# P5a_Filter1A.net
KiCad netlist of a schematic drawn in Altium Designer
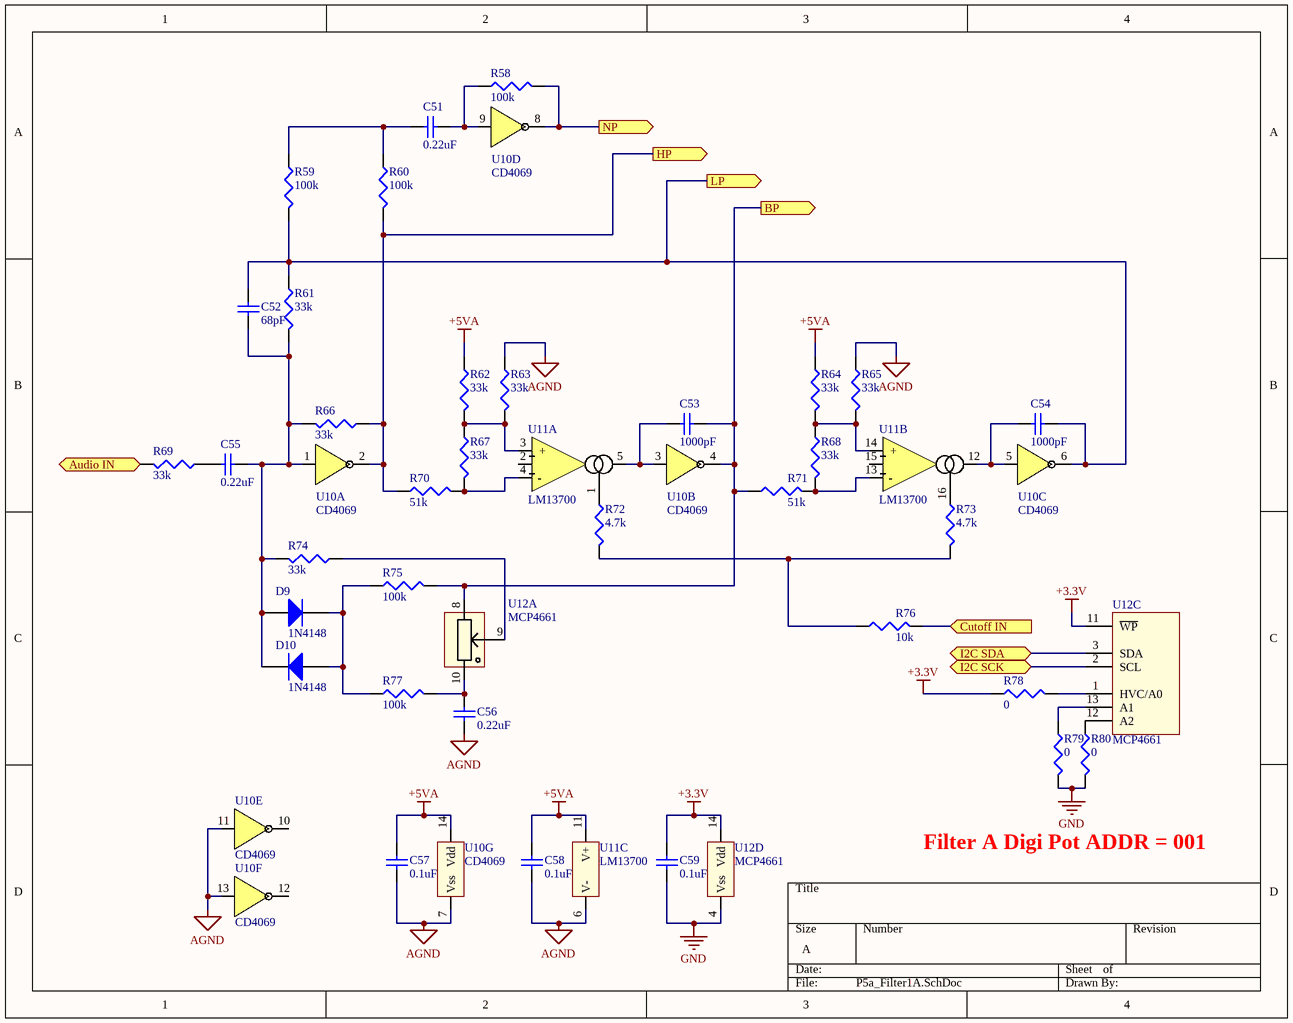
[diagram p0: P5a_Filter1A.SchDoc]

(export (version "E")
  (design (tool "Eeschema 10.0.6"))
  (components
    (comp (ref "C51")
      (value "0.22uF")
      (footprint "CAP 0603 (1608 metric)")
      (description "Capacitor (Semiconductor SIM Model)")
      (libsource (lib "Miscellaneous Devices") (part "Cap Semi"))
    )
    (comp (ref "C52")
      (value "68pF")
      (footprint "CAP 0603 (1608 metric)")
      (description "Capacitor (Semiconductor SIM Model)")
      (libsource (lib "Miscellaneous Devices") (part "Cap Semi"))
    )
    (comp (ref "C53")
      (value "1000pF")
      (footprint "CAP 0603 (1608 metric)")
      (description "Capacitor (Semiconductor SIM Model)")
      (libsource (lib "Miscellaneous Devices") (part "Cap Semi"))
    )
    (comp (ref "C54")
      (value "1000pF")
      (footprint "CAP 0603 (1608 metric)")
      (description "Capacitor (Semiconductor SIM Model)")
      (libsource (lib "Miscellaneous Devices") (part "Cap Semi"))
    )
    (comp (ref "C55")
      (value "0.22uF")
      (footprint "CAP 0603 (1608 metric)")
      (description "Capacitor (Semiconductor SIM Model)")
      (libsource (lib "Miscellaneous Devices") (part "Cap Semi"))
    )
    (comp (ref "C56")
      (value "0.22uF")
      (footprint "CAP 0603 (1608 metric)")
      (description "Capacitor (Semiconductor SIM Model)")
      (libsource (lib "Miscellaneous Devices") (part "Cap Semi"))
    )
    (comp (ref "C57")
      (value "0.1uF")
      (footprint "CAP 0603 (1608 metric)")
      (description "Capacitor (Semiconductor SIM Model)")
      (libsource (lib "Miscellaneous Devices") (part "Cap Semi"))
    )
    (comp (ref "C58")
      (value "0.1uF")
      (footprint "CAP 0603 (1608 metric)")
      (description "Capacitor (Semiconductor SIM Model)")
      (libsource (lib "Miscellaneous Devices") (part "Cap Semi"))
    )
    (comp (ref "C59")
      (value "0.1uF")
      (footprint "CAP 0603 (1608 metric)")
      (description "Capacitor (Semiconductor SIM Model)")
      (libsource (lib "Miscellaneous Devices") (part "Cap Semi"))
    )
    (comp (ref "D9")
      (value "1N4148")
      (description "High Conductance Fast Diode")
      (libsource (lib "Miscellaneous Devices") (part "Diode 1N4148"))
    )
    (comp (ref "D10")
      (value "1N4148")
      (description "High Conductance Fast Diode")
      (libsource (lib "Miscellaneous Devices") (part "Diode 1N4148"))
    )
    (comp (ref "R58")
      (value "100k")
      (footprint "RES 0603 (1608 metric)")
      (description "Resistor")
      (libsource (lib "Miscellaneous Devices") (part "Res3"))
    )
    (comp (ref "R59")
      (value "100k")
      (footprint "RES 0603 (1608 metric)")
      (description "Resistor")
      (libsource (lib "Miscellaneous Devices") (part "Res3"))
    )
    (comp (ref "R60")
      (value "100k")
      (footprint "RES 0603 (1608 metric)")
      (description "Resistor")
      (libsource (lib "Miscellaneous Devices") (part "Res3"))
    )
    (comp (ref "R61")
      (value "33k")
      (footprint "RES 0603 (1608 metric)")
      (description "Resistor")
      (libsource (lib "Miscellaneous Devices") (part "Res3"))
    )
    (comp (ref "R62")
      (value "33k")
      (footprint "RES 0603 (1608 metric)")
      (description "Resistor")
      (libsource (lib "Miscellaneous Devices") (part "Res3"))
    )
    (comp (ref "R63")
      (value "33k")
      (footprint "RES 0603 (1608 metric)")
      (description "Resistor")
      (libsource (lib "Miscellaneous Devices") (part "Res3"))
    )
    (comp (ref "R64")
      (value "33k")
      (footprint "RES 0603 (1608 metric)")
      (description "Resistor")
      (libsource (lib "Miscellaneous Devices") (part "Res3"))
    )
    (comp (ref "R65")
      (value "33k")
      (footprint "RES 0603 (1608 metric)")
      (description "Resistor")
      (libsource (lib "Miscellaneous Devices") (part "Res3"))
    )
    (comp (ref "R66")
      (value "33k")
      (footprint "RES 0603 (1608 metric)")
      (description "Resistor")
      (libsource (lib "Miscellaneous Devices") (part "Res3"))
    )
    (comp (ref "R67")
      (value "33k")
      (footprint "RES 0603 (1608 metric)")
      (description "Resistor")
      (libsource (lib "Miscellaneous Devices") (part "Res3"))
    )
    (comp (ref "R68")
      (value "33k")
      (footprint "RES 0603 (1608 metric)")
      (description "Resistor")
      (libsource (lib "Miscellaneous Devices") (part "Res3"))
    )
    (comp (ref "R69")
      (value "33k")
      (footprint "RES 0603 (1608 metric)")
      (description "Resistor")
      (libsource (lib "Miscellaneous Devices") (part "Res3"))
    )
    (comp (ref "R70")
      (value "51k")
      (footprint "RES 0603 (1608 metric)")
      (description "Resistor")
      (libsource (lib "Miscellaneous Devices") (part "Res3"))
    )
    (comp (ref "R71")
      (value "51k")
      (footprint "RES 0603 (1608 metric)")
      (description "Resistor")
      (libsource (lib "Miscellaneous Devices") (part "Res3"))
    )
    (comp (ref "R72")
      (value "4.7k")
      (footprint "RES 0603 (1608 metric)")
      (description "Resistor")
      (libsource (lib "Miscellaneous Devices") (part "Res3"))
    )
    (comp (ref "R73")
      (value "4.7k")
      (footprint "RES 0603 (1608 metric)")
      (description "Resistor")
      (libsource (lib "Miscellaneous Devices") (part "Res3"))
    )
    (comp (ref "R74")
      (value "33k")
      (footprint "RES 0603 (1608 metric)")
      (description "Resistor")
      (libsource (lib "Miscellaneous Devices") (part "Res3"))
    )
    (comp (ref "R75")
      (value "100k")
      (footprint "RES 0603 (1608 metric)")
      (description "Resistor")
      (libsource (lib "Miscellaneous Devices") (part "Res3"))
    )
    (comp (ref "R76")
      (value "10k")
      (footprint "RES 0603 (1608 metric)")
      (description "Resistor")
      (libsource (lib "Miscellaneous Devices") (part "Res3"))
    )
    (comp (ref "R77")
      (value "100k")
      (footprint "RES 0603 (1608 metric)")
      (description "Resistor")
      (libsource (lib "Miscellaneous Devices") (part "Res3"))
    )
    (comp (ref "R78")
      (value "0")
      (footprint "RES 0603 (1608 metric)")
      (description "Resistor")
      (libsource (lib "Miscellaneous Devices") (part "Res3"))
    )
    (comp (ref "R79")
      (value "0")
      (footprint "RES 0603 (1608 metric)")
      (description "Resistor")
      (libsource (lib "Miscellaneous Devices") (part "Res3"))
    )
    (comp (ref "R80")
      (value "0")
      (footprint "RES 0603 (1608 metric)")
      (description "Resistor")
      (libsource (lib "Miscellaneous Devices") (part "Res3"))
    )
    (comp (ref "U10")
      (value "CD4069")
      (description "Hex Inverter")
      (libsource (lib "FilterPoC") (part "CD4069"))
    )
    (comp (ref "U11")
      (value "LM13700")
      (description "Dual Transconductance OpAmp")
      (libsource (lib "FilterPoC") (part "LM13700M"))
    )
    (comp (ref "U12")
      (value "MCP4661")
      (description "Dual DigiPot non volatile I2C")
      (libsource (lib "FilterPoC") (part "MCP4661"))
    )
  )
  (nets
    (net (code "1") (name "+3.3V") (class "Default")
      (node (ref "C59") (pin "1") (pinfunction "1_1") (pintype "passive"))
      (node (ref "R78") (pin "1") (pinfunction "1_1") (pintype "passive"))
      (node (ref "U12") (pin "11") (pinfunction "~{WP}_11") (pintype "passive"))
      (node (ref "U12") (pin "14") (pinfunction "Vdd_14") (pintype "power_in"))
    )
    (net (code "2") (name "+5VA") (class "Default")
      (node (ref "C57") (pin "1") (pinfunction "1_1") (pintype "passive"))
      (node (ref "C58") (pin "1") (pinfunction "1_1") (pintype "passive"))
      (node (ref "R62") (pin "1") (pinfunction "1_1") (pintype "passive"))
      (node (ref "R64") (pin "1") (pinfunction "1_1") (pintype "passive"))
      (node (ref "U10") (pin "14") (pinfunction "Vdd_14") (pintype "power_in"))
      (node (ref "U11") (pin "11") (pinfunction "V+_11") (pintype "power_in"))
    )
    (net (code "3") (name "/Audio IN") (class "Default")
      (node (ref "R69") (pin "2") (pinfunction "2_2") (pintype "passive"))
    )
    (net (code "4") (name "/BP") (class "Default")
      (node (ref "C53") (pin "2") (pinfunction "2_2") (pintype "passive"))
      (node (ref "R71") (pin "1") (pinfunction "1_1") (pintype "passive"))
      (node (ref "R75") (pin "2") (pinfunction "2_2") (pintype "passive"))
      (node (ref "U10") (pin "4") (pinfunction "~{B}_4") (pintype "passive"))
      (node (ref "U12") (pin "8") (pinfunction "P0A_8") (pintype "passive"))
    )
    (net (code "5") (name "/Cutoff IN") (class "Default")
      (node (ref "R76") (pin "2") (pinfunction "2_2") (pintype "passive"))
    )
    (net (code "6") (name "/HP") (class "Default")
      (node (ref "R60") (pin "2") (pinfunction "2_2") (pintype "passive"))
      (node (ref "R66") (pin "1") (pinfunction "1_1") (pintype "passive"))
      (node (ref "R70") (pin "1") (pinfunction "1_1") (pintype "passive"))
      (node (ref "U10") (pin "2") (pinfunction "~{A}_2") (pintype "passive"))
    )
    (net (code "7") (name "/I2C SCK") (class "Default")
      (node (ref "U12") (pin "2") (pinfunction "SCL_2") (pintype "passive"))
    )
    (net (code "8") (name "/I2C SDA") (class "Default")
      (node (ref "U12") (pin "3") (pinfunction "SDA_3") (pintype "passive"))
    )
    (net (code "9") (name "/LP") (class "Default")
      (node (ref "C52") (pin "2") (pinfunction "2_2") (pintype "passive"))
      (node (ref "C54") (pin "2") (pinfunction "2_2") (pintype "passive"))
      (node (ref "R59") (pin "2") (pinfunction "2_2") (pintype "passive"))
      (node (ref "R61") (pin "1") (pinfunction "1_1") (pintype "passive"))
      (node (ref "U10") (pin "6") (pinfunction "~{C}_6") (pintype "passive"))
    )
    (net (code "10") (name "/NP") (class "Default")
      (node (ref "R58") (pin "2") (pinfunction "2_2") (pintype "passive"))
      (node (ref "U10") (pin "8") (pinfunction "~{D}_8") (pintype "passive"))
    )
    (net (code "11") (name "AGND") (class "Default")
      (node (ref "C56") (pin "2") (pinfunction "2_2") (pintype "passive"))
      (node (ref "C57") (pin "2") (pinfunction "2_2") (pintype "passive"))
      (node (ref "C58") (pin "2") (pinfunction "2_2") (pintype "passive"))
      (node (ref "R63") (pin "1") (pinfunction "1_1") (pintype "passive"))
      (node (ref "R65") (pin "1") (pinfunction "1_1") (pintype "passive"))
      (node (ref "U10") (pin "11") (pinfunction "E_11") (pintype "passive"))
      (node (ref "U10") (pin "13") (pinfunction "F_13") (pintype "passive"))
      (node (ref "U10") (pin "7") (pinfunction "Vss_7") (pintype "power_in"))
      (node (ref "U11") (pin "6") (pinfunction "V-_6") (pintype "power_in"))
    )
    (net (code "12") (name "GND") (class "Default")
      (node (ref "C59") (pin "2") (pinfunction "2_2") (pintype "passive"))
      (node (ref "R79") (pin "2") (pinfunction "2_2") (pintype "passive"))
      (node (ref "R80") (pin "2") (pinfunction "2_2") (pintype "passive"))
      (node (ref "U12") (pin "4") (pinfunction "Vss_4") (pintype "power_in"))
    )
    (net (code "13") (name "Net-(C51-Pad1)") (class "Default")
      (node (ref "C51") (pin "1") (pinfunction "1_1") (pintype "passive"))
      (node (ref "R59") (pin "1") (pinfunction "1_1") (pintype "passive"))
      (node (ref "R60") (pin "1") (pinfunction "1_1") (pintype "passive"))
    )
    (net (code "14") (name "Net-(C55-Pad1)") (class "Default")
      (node (ref "C55") (pin "1") (pinfunction "1_1") (pintype "passive"))
      (node (ref "R69") (pin "1") (pinfunction "1_1") (pintype "passive"))
    )
    (net (code "15") (name "Net-(D10-A)") (class "Default")
      (node (ref "D10") (pin "1") (pinfunction "A_1") (pintype "passive"))
      (node (ref "D9") (pin "2") (pinfunction "K_2") (pintype "passive"))
      (node (ref "R75") (pin "1") (pinfunction "1_1") (pintype "passive"))
      (node (ref "R77") (pin "1") (pinfunction "1_1") (pintype "passive"))
    )
    (net (code "16") (name "Net-(D10-K)") (class "Default")
      (node (ref "C52") (pin "1") (pinfunction "1_1") (pintype "passive"))
      (node (ref "C55") (pin "2") (pinfunction "2_2") (pintype "passive"))
      (node (ref "D10") (pin "2") (pinfunction "K_2") (pintype "passive"))
      (node (ref "D9") (pin "1") (pinfunction "A_1") (pintype "passive"))
      (node (ref "R61") (pin "2") (pinfunction "2_2") (pintype "passive"))
      (node (ref "R66") (pin "2") (pinfunction "2_2") (pintype "passive"))
      (node (ref "R74") (pin "2") (pinfunction "2_2") (pintype "passive"))
      (node (ref "U10") (pin "1") (pinfunction "A_1") (pintype "passive"))
    )
    (net (code "17") (name "Net-(R72-Pad2)") (class "Default")
      (node (ref "R72") (pin "2") (pinfunction "2_2") (pintype "passive"))
      (node (ref "R73") (pin "2") (pinfunction "2_2") (pintype "passive"))
      (node (ref "R76") (pin "1") (pinfunction "1_1") (pintype "passive"))
    )
    (net (code "18") (name "Net-(U10B-B)") (class "Default")
      (node (ref "C53") (pin "1") (pinfunction "1_1") (pintype "passive"))
      (node (ref "U10") (pin "3") (pinfunction "B_3") (pintype "passive"))
      (node (ref "U11") (pin "5") (pinfunction "OUT_5") (pintype "passive"))
    )
    (net (code "19") (name "Net-(U10C-C)") (class "Default")
      (node (ref "C54") (pin "1") (pinfunction "1_1") (pintype "passive"))
      (node (ref "U10") (pin "5") (pinfunction "C_5") (pintype "passive"))
      (node (ref "U11") (pin "12") (pinfunction "OUT_12") (pintype "passive"))
    )
    (net (code "20") (name "Net-(U10D-D)") (class "Default")
      (node (ref "C51") (pin "2") (pinfunction "2_2") (pintype "passive"))
      (node (ref "R58") (pin "1") (pinfunction "1_1") (pintype "passive"))
      (node (ref "U10") (pin "9") (pinfunction "D_9") (pintype "passive"))
    )
    (net (code "21") (name "Net-(U11A-+)") (class "Default")
      (node (ref "R62") (pin "2") (pinfunction "2_2") (pintype "passive"))
      (node (ref "R63") (pin "2") (pinfunction "2_2") (pintype "passive"))
      (node (ref "R67") (pin "1") (pinfunction "1_1") (pintype "passive"))
      (node (ref "U11") (pin "3") (pinfunction "+_3") (pintype "passive"))
    )
    (net (code "22") (name "Net-(U11A--)") (class "Default")
      (node (ref "R67") (pin "2") (pinfunction "2_2") (pintype "passive"))
      (node (ref "R70") (pin "2") (pinfunction "2_2") (pintype "passive"))
      (node (ref "U11") (pin "4") (pinfunction "-_4") (pintype "passive"))
    )
    (net (code "23") (name "Net-(U11A-BIAS)") (class "Default")
      (node (ref "R72") (pin "1") (pinfunction "1_1") (pintype "passive"))
      (node (ref "U11") (pin "1") (pinfunction "BIAS_1") (pintype "passive"))
    )
    (net (code "24") (name "Net-(U11B-+)") (class "Default")
      (node (ref "R64") (pin "2") (pinfunction "2_2") (pintype "passive"))
      (node (ref "R65") (pin "2") (pinfunction "2_2") (pintype "passive"))
      (node (ref "R68") (pin "1") (pinfunction "1_1") (pintype "passive"))
      (node (ref "U11") (pin "14") (pinfunction "+_14") (pintype "passive"))
    )
    (net (code "25") (name "Net-(U11B--)") (class "Default")
      (node (ref "R68") (pin "2") (pinfunction "2_2") (pintype "passive"))
      (node (ref "R71") (pin "2") (pinfunction "2_2") (pintype "passive"))
      (node (ref "U11") (pin "13") (pinfunction "-_13") (pintype "passive"))
    )
    (net (code "26") (name "Net-(U11B-BIAS)") (class "Default")
      (node (ref "R73") (pin "1") (pinfunction "1_1") (pintype "passive"))
      (node (ref "U11") (pin "16") (pinfunction "BIAS_16") (pintype "passive"))
    )
    (net (code "27") (name "Net-(U12A-P0B)") (class "Default")
      (node (ref "C56") (pin "1") (pinfunction "1_1") (pintype "passive"))
      (node (ref "R77") (pin "2") (pinfunction "2_2") (pintype "passive"))
      (node (ref "U12") (pin "10") (pinfunction "P0B_10") (pintype "passive"))
    )
    (net (code "28") (name "Net-(U12A-P0W)") (class "Default")
      (node (ref "R74") (pin "1") (pinfunction "1_1") (pintype "passive"))
      (node (ref "U12") (pin "9") (pinfunction "P0W_9") (pintype "passive"))
    )
    (net (code "29") (name "Net-(U12C-A1)") (class "Default")
      (node (ref "R79") (pin "1") (pinfunction "1_1") (pintype "passive"))
      (node (ref "U12") (pin "13") (pinfunction "A1_13") (pintype "power_in"))
    )
    (net (code "30") (name "Net-(U12C-A2)") (class "Default")
      (node (ref "R80") (pin "1") (pinfunction "1_1") (pintype "passive"))
      (node (ref "U12") (pin "12") (pinfunction "A2_12") (pintype "power_in"))
    )
    (net (code "31") (name "Net-(U12C-HVC{slash}A0)") (class "Default")
      (node (ref "R78") (pin "2") (pinfunction "2_2") (pintype "passive"))
      (node (ref "U12") (pin "1") (pinfunction "HVC/A0_1") (pintype "power_in"))
    )
    (net (code "32") (name "unconnected-(U10E-~{E}-Pad10)") (class "Default")
      (node (ref "U10") (pin "10") (pinfunction "~{E}_10") (pintype "passive"))
    )
    (net (code "33") (name "unconnected-(U10F-~{F}-Pad12)") (class "Default")
      (node (ref "U10") (pin "12") (pinfunction "~{F}_12") (pintype "passive"))
    )
    (net (code "34") (name "unconnected-(U11A-Diode_BIAS-Pad2)") (class "Default")
      (node (ref "U11") (pin "2") (pinfunction "Diode_BIAS_2") (pintype "passive"))
    )
    (net (code "35") (name "unconnected-(U11B-Diode_BIAS-Pad15)") (class "Default")
      (node (ref "U11") (pin "15") (pinfunction "Diode_BIAS_15") (pintype "passive"))
    )
  )
)
